# Schematic_AddKEYSTM32_EASYEDA.net
KiCad netlist of a schematic drawn in EasyEDA
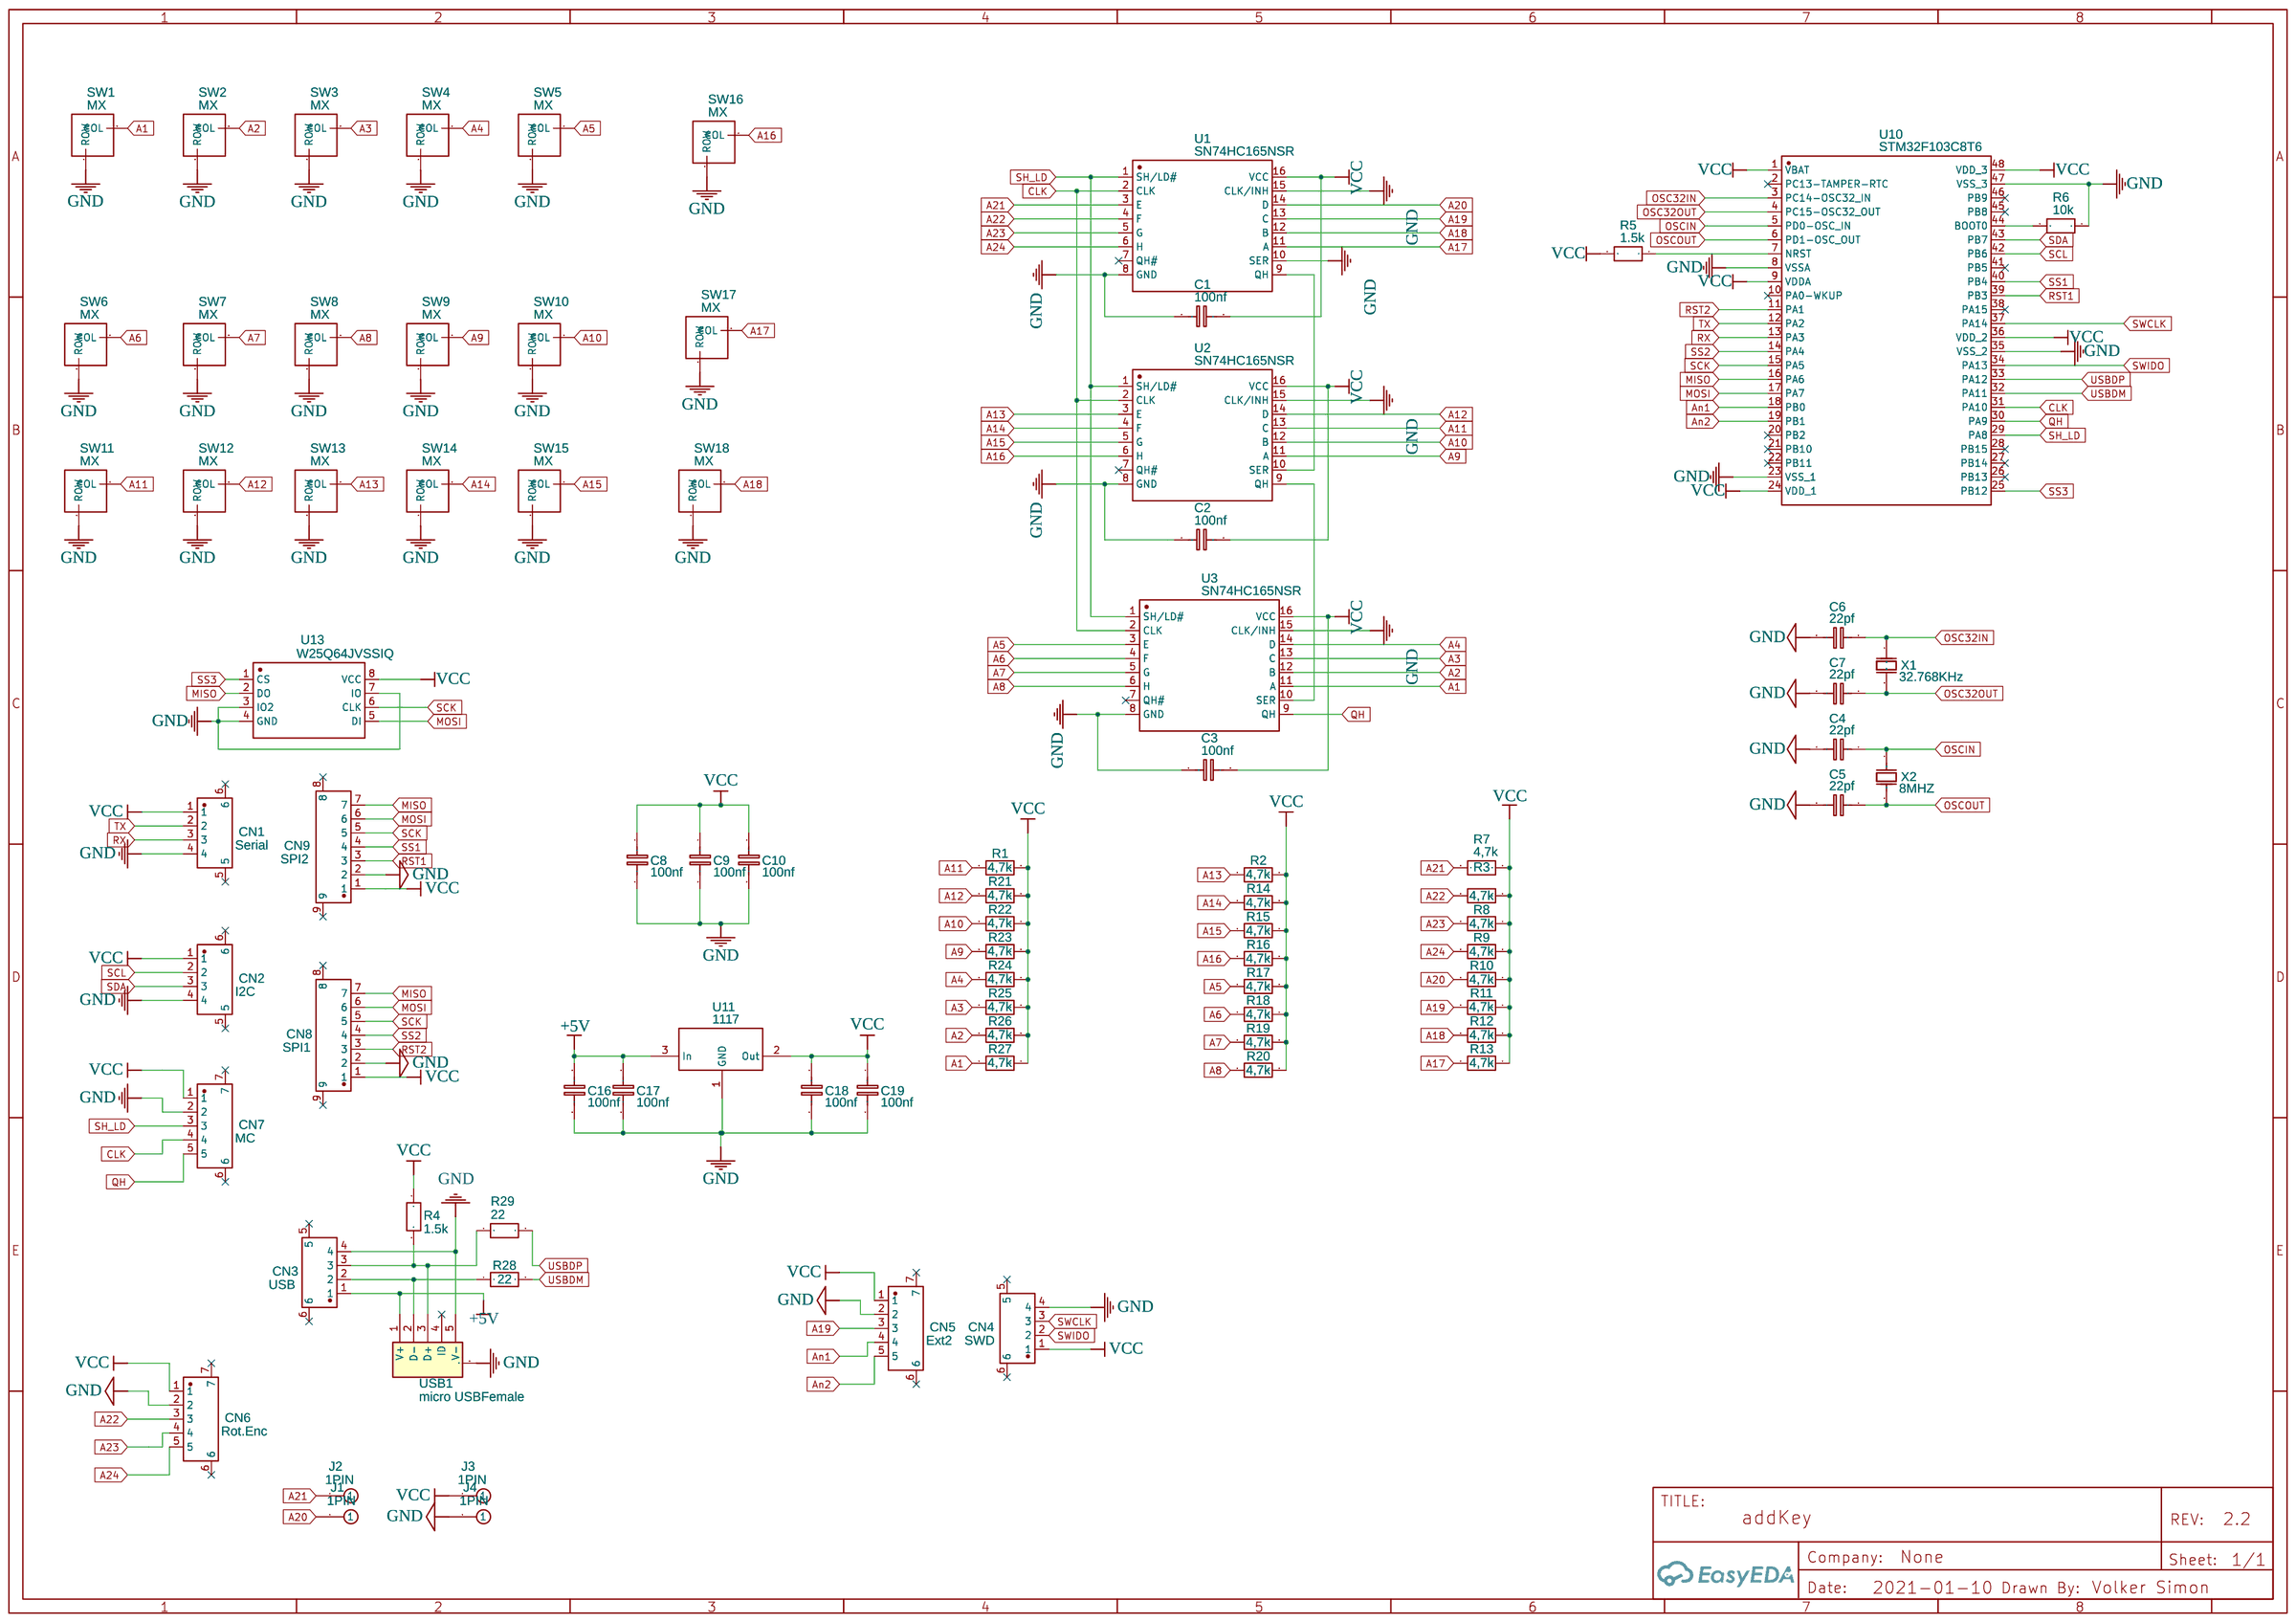
[diagram p0: schematic sheet]

(export (version "E")
  (design (tool "Eeschema 10.0.6"))
  (components
    (comp (ref "C1")
      (value "100nf")
      (fields
        (field (name "BOM_Manufacturer Part") "1206F104M500NT")
        (field (name "BOM_Supplier Part") "C313097")
      )
      (libsource (lib "") (part "Cap_1206_EU_4"))
    )
    (comp (ref "C2")
      (value "100nf")
      (fields
        (field (name "BOM_Manufacturer Part") "1206F104M500NT")
        (field (name "BOM_Supplier Part") "C313097")
      )
      (libsource (lib "") (part "Cap_1206_EU_4"))
    )
    (comp (ref "C3")
      (value "100nf")
      (fields
        (field (name "BOM_Manufacturer Part") "1206F104M500NT")
        (field (name "BOM_Supplier Part") "C313097")
      )
      (libsource (lib "") (part "Cap_1206_EU_3"))
    )
    (comp (ref "C4")
      (value "22pf")
      (fields
        (field (name "BOM_Manufacturer Part") "1206CG220J102NT")
        (field (name "BOM_Supplier Part") "C313096")
      )
      (libsource (lib "") (part "Cap_1206_EU"))
    )
    (comp (ref "C5")
      (value "22pf")
      (fields
        (field (name "BOM_Manufacturer Part") "1206CG220J102NT")
        (field (name "BOM_Supplier Part") "C313096")
      )
      (libsource (lib "") (part "Cap_1206_EU"))
    )
    (comp (ref "C6")
      (value "22pf")
      (fields
        (field (name "BOM_Manufacturer Part") "1206CG220J102NT")
        (field (name "BOM_Supplier Part") "C313096")
      )
      (libsource (lib "") (part "Cap_1206_EU_1"))
    )
    (comp (ref "C7")
      (value "22pf")
      (fields
        (field (name "BOM_Manufacturer Part") "1206CG220J102NT")
        (field (name "BOM_Supplier Part") "C313096")
      )
      (libsource (lib "") (part "Cap_1206_EU_1"))
    )
    (comp (ref "C8")
      (value "100nf")
      (fields
        (field (name "BOM_Manufacturer Part") "1206F104M500NT")
        (field (name "BOM_Supplier Part") "C313097")
      )
      (libsource (lib "") (part "Cap_1206_EU_2"))
    )
    (comp (ref "C9")
      (value "100nf")
      (fields
        (field (name "BOM_Manufacturer Part") "1206F104M500NT")
        (field (name "BOM_Supplier Part") "C313097")
      )
      (libsource (lib "") (part "Cap_1206_EU_2"))
    )
    (comp (ref "C10")
      (value "100nf")
      (fields
        (field (name "BOM_Manufacturer Part") "1206F104M500NT")
        (field (name "BOM_Supplier Part") "C313097")
      )
      (libsource (lib "") (part "Cap_1206_EU_5"))
    )
    (comp (ref "C16")
      (value "100nf")
      (fields
        (field (name "BOM_Manufacturer Part") "1206F104M500NT")
        (field (name "BOM_Supplier Part") "C313097")
      )
      (libsource (lib "") (part "Cap_1206_EU_2"))
    )
    (comp (ref "C17")
      (value "100nf")
      (fields
        (field (name "BOM_Manufacturer Part") "1206F104M500NT")
        (field (name "BOM_Supplier Part") "C313097")
      )
      (libsource (lib "") (part "Cap_1206_EU_2"))
    )
    (comp (ref "C18")
      (value "100nf")
      (fields
        (field (name "BOM_Manufacturer Part") "1206F104M500NT")
        (field (name "BOM_Supplier Part") "C313097")
      )
      (libsource (lib "") (part "Cap_1206_EU_5"))
    )
    (comp (ref "C19")
      (value "100nf")
      (fields
        (field (name "BOM_Manufacturer Part") "1206F104M500NT")
        (field (name "BOM_Supplier Part") "C313097")
      )
      (libsource (lib "") (part "Cap_1206_EU_5"))
    )
    (comp (ref "CN1")
      (value "Serial")
      (fields
        (field (name "BOM_Manufacturer Part") "X1002WRS-04E-LPSWHF")
        (field (name "BOM_Supplier Part") "C437064")
      )
      (libsource (lib "") (part "X1002WRS-04E-LPSWHF"))
    )
    (comp (ref "CN2")
      (value "I2C")
      (fields
        (field (name "BOM_Manufacturer Part") "X1002WRS-04E-LPSWHF")
        (field (name "BOM_Supplier Part") "C437064")
      )
      (libsource (lib "") (part "X1002WRS-04E-LPSWHF"))
    )
    (comp (ref "CN3")
      (value "USB")
      (fields
        (field (name "BOM_Manufacturer Part") "X1002WRS-04E-LPSWHF")
        (field (name "BOM_Supplier Part") "C437064")
      )
      (libsource (lib "") (part "X1002WRS-04E-LPSWHF_1"))
    )
    (comp (ref "CN4")
      (value "SWD")
      (fields
        (field (name "BOM_Manufacturer Part") "X1002WRS-04E-LPSWHF")
        (field (name "BOM_Supplier Part") "C437064")
      )
      (libsource (lib "") (part "X1002WRS-04E-LPSWHF_1"))
    )
    (comp (ref "CN5")
      (value "Ext2")
      (fields
        (field (name "BOM_Manufacturer Part") "X1002WRS-05E-LPSWHF")
        (field (name "BOM_Supplier Part") "C437065")
      )
      (libsource (lib "") (part "X1002WRS-05E-LPSWHF"))
    )
    (comp (ref "CN6")
      (value "Rot.Enc")
      (fields
        (field (name "BOM_Manufacturer Part") "X1002WRS-05E-LPSWHF")
        (field (name "BOM_Supplier Part") "C437065")
      )
      (libsource (lib "") (part "X1002WRS-05E-LPSWHF"))
    )
    (comp (ref "CN7")
      (value "MC")
      (fields
        (field (name "BOM_Manufacturer Part") "X1002WRS-05E-LPSWHF")
        (field (name "BOM_Supplier Part") "C437065")
      )
      (libsource (lib "") (part "X1002WRS-05E-LPSWHF"))
    )
    (comp (ref "CN8")
      (value "SPI1")
      (fields
        (field (name "BOM_Manufacturer Part") "X1002WRS-07E-LPSWHF")
        (field (name "BOM_Supplier Part") "C437067")
      )
      (libsource (lib "") (part "X1002WRS-07E-LPSWHF"))
    )
    (comp (ref "CN9")
      (value "SPI2")
      (fields
        (field (name "BOM_Manufacturer Part") "X1002WRS-07E-LPSWHF")
        (field (name "BOM_Supplier Part") "C437067")
      )
      (libsource (lib "") (part "X1002WRS-07E-LPSWHF"))
    )
    (comp (ref "J1") (value "1PIN") (libsource (lib "") (part "1PIN")))
    (comp (ref "J2") (value "1PIN") (libsource (lib "") (part "1PIN")))
    (comp (ref "J3") (value "1PIN") (libsource (lib "") (part "1PIN")))
    (comp (ref "J4") (value "1PIN") (libsource (lib "") (part "1PIN")))
    (comp (ref "R1")
      (value "4,7k")
      (fields
        (field (name "BOM_Manufacturer Part") "1206W4F4701T5E")
        (field (name "BOM_Supplier Part") "C17936")
      )
      (libsource (lib "") (part "Res_AXIAL-0.3(1/8W)_EU"))
    )
    (comp (ref "R2")
      (value "4,7k")
      (fields
        (field (name "BOM_Manufacturer Part") "1206W4F4701T5E")
        (field (name "BOM_Supplier Part") "C17936")
      )
      (libsource (lib "") (part "Res_AXIAL-0.3(1/8W)_EU"))
    )
    (comp (ref "R3")
      (value "4,7k")
      (fields
        (field (name "BOM_Manufacturer Part") "1206W4F4701T5E")
        (field (name "BOM_Supplier Part") "C17936")
      )
      (libsource (lib "") (part "Res_AXIAL-0.3(1/8W)_EU"))
    )
    (comp (ref "R4") (value "1.5k") (libsource (lib "") (part "Res_AXIAL-0.3(1/8W)_EU_1")))
    (comp (ref "R5") (value "1.5k") (libsource (lib "") (part "Res_AXIAL-0.3(1/8W)_EU")))
    (comp (ref "R6") (value "10k") (libsource (lib "") (part "Res_AXIAL-0.3(1/8W)_EU")))
    (comp (ref "R7")
      (value "4,7k")
      (fields
        (field (name "BOM_Manufacturer Part") "1206W4F4701T5E")
        (field (name "BOM_Supplier Part") "C17936")
      )
      (libsource (lib "") (part "Res_AXIAL-0.3(1/8W)_EU"))
    )
    (comp (ref "R8")
      (value "4,7k")
      (fields
        (field (name "BOM_Manufacturer Part") "1206W4F4701T5E")
        (field (name "BOM_Supplier Part") "C17936")
      )
      (libsource (lib "") (part "Res_AXIAL-0.3(1/8W)_EU"))
    )
    (comp (ref "R9")
      (value "4,7k")
      (fields
        (field (name "BOM_Manufacturer Part") "1206W4F4701T5E")
        (field (name "BOM_Supplier Part") "C17936")
      )
      (libsource (lib "") (part "Res_AXIAL-0.3(1/8W)_EU"))
    )
    (comp (ref "R10")
      (value "4,7k")
      (fields
        (field (name "BOM_Manufacturer Part") "1206W4F4701T5E")
        (field (name "BOM_Supplier Part") "C17936")
      )
      (libsource (lib "") (part "Res_AXIAL-0.3(1/8W)_EU"))
    )
    (comp (ref "R11")
      (value "4,7k")
      (fields
        (field (name "BOM_Manufacturer Part") "1206W4F4701T5E")
        (field (name "BOM_Supplier Part") "C17936")
      )
      (libsource (lib "") (part "Res_AXIAL-0.3(1/8W)_EU"))
    )
    (comp (ref "R12")
      (value "4,7k")
      (fields
        (field (name "BOM_Manufacturer Part") "1206W4F4701T5E")
        (field (name "BOM_Supplier Part") "C17936")
      )
      (libsource (lib "") (part "Res_AXIAL-0.3(1/8W)_EU"))
    )
    (comp (ref "R13")
      (value "4,7k")
      (fields
        (field (name "BOM_Manufacturer Part") "1206W4F4701T5E")
        (field (name "BOM_Supplier Part") "C17936")
      )
      (libsource (lib "") (part "Res_AXIAL-0.3(1/8W)_EU"))
    )
    (comp (ref "R14")
      (value "4,7k")
      (fields
        (field (name "BOM_Manufacturer Part") "1206W4F4701T5E")
        (field (name "BOM_Supplier Part") "C17936")
      )
      (libsource (lib "") (part "Res_AXIAL-0.3(1/8W)_EU"))
    )
    (comp (ref "R15")
      (value "4,7k")
      (fields
        (field (name "BOM_Manufacturer Part") "1206W4F4701T5E")
        (field (name "BOM_Supplier Part") "C17936")
      )
      (libsource (lib "") (part "Res_AXIAL-0.3(1/8W)_EU"))
    )
    (comp (ref "R16")
      (value "4,7k")
      (fields
        (field (name "BOM_Manufacturer Part") "1206W4F4701T5E")
        (field (name "BOM_Supplier Part") "C17936")
      )
      (libsource (lib "") (part "Res_AXIAL-0.3(1/8W)_EU"))
    )
    (comp (ref "R17")
      (value "4,7k")
      (fields
        (field (name "BOM_Manufacturer Part") "1206W4F4701T5E")
        (field (name "BOM_Supplier Part") "C17936")
      )
      (libsource (lib "") (part "Res_AXIAL-0.3(1/8W)_EU"))
    )
    (comp (ref "R18")
      (value "4,7k")
      (fields
        (field (name "BOM_Manufacturer Part") "1206W4F4701T5E")
        (field (name "BOM_Supplier Part") "C17936")
      )
      (libsource (lib "") (part "Res_AXIAL-0.3(1/8W)_EU"))
    )
    (comp (ref "R19")
      (value "4,7k")
      (fields
        (field (name "BOM_Manufacturer Part") "1206W4F4701T5E")
        (field (name "BOM_Supplier Part") "C17936")
      )
      (libsource (lib "") (part "Res_AXIAL-0.3(1/8W)_EU"))
    )
    (comp (ref "R20")
      (value "4,7k")
      (fields
        (field (name "BOM_Manufacturer Part") "1206W4F4701T5E")
        (field (name "BOM_Supplier Part") "C17936")
      )
      (libsource (lib "") (part "Res_AXIAL-0.3(1/8W)_EU"))
    )
    (comp (ref "R21")
      (value "4,7k")
      (fields
        (field (name "BOM_Manufacturer Part") "1206W4F4701T5E")
        (field (name "BOM_Supplier Part") "C17936")
      )
      (libsource (lib "") (part "Res_AXIAL-0.3(1/8W)_EU"))
    )
    (comp (ref "R22")
      (value "4,7k")
      (fields
        (field (name "BOM_Manufacturer Part") "1206W4F4701T5E")
        (field (name "BOM_Supplier Part") "C17936")
      )
      (libsource (lib "") (part "Res_AXIAL-0.3(1/8W)_EU"))
    )
    (comp (ref "R23")
      (value "4,7k")
      (fields
        (field (name "BOM_Manufacturer Part") "1206W4F4701T5E")
        (field (name "BOM_Supplier Part") "C17936")
      )
      (libsource (lib "") (part "Res_AXIAL-0.3(1/8W)_EU"))
    )
    (comp (ref "R24")
      (value "4,7k")
      (fields
        (field (name "BOM_Manufacturer Part") "1206W4F4701T5E")
        (field (name "BOM_Supplier Part") "C17936")
      )
      (libsource (lib "") (part "Res_AXIAL-0.3(1/8W)_EU"))
    )
    (comp (ref "R25")
      (value "4,7k")
      (fields
        (field (name "BOM_Manufacturer Part") "1206W4F4701T5E")
        (field (name "BOM_Supplier Part") "C17936")
      )
      (libsource (lib "") (part "Res_AXIAL-0.3(1/8W)_EU"))
    )
    (comp (ref "R26")
      (value "4,7k")
      (fields
        (field (name "BOM_Manufacturer Part") "1206W4F4701T5E")
        (field (name "BOM_Supplier Part") "C17936")
      )
      (libsource (lib "") (part "Res_AXIAL-0.3(1/8W)_EU"))
    )
    (comp (ref "R27")
      (value "4,7k")
      (fields
        (field (name "BOM_Manufacturer Part") "1206W4F4701T5E")
        (field (name "BOM_Supplier Part") "C17936")
      )
      (libsource (lib "") (part "Res_AXIAL-0.3(1/8W)_EU"))
    )
    (comp (ref "R28") (value "22") (libsource (lib "") (part "Res_AXIAL-0.3(1/8W)_EU_2")))
    (comp (ref "R29") (value "22") (libsource (lib "") (part "Res_AXIAL-0.3(1/8W)_EU_2")))
    (comp (ref "SW1")
      (value "MX")
      (fields (field (name "BOM_Manufacturer Part") "Cherry") (field (name "BOM_Supplier Part") "CH310-ND"))
      (libsource (lib "") (part "CHERRY MX SWITCH 1.0U"))
    )
    (comp (ref "SW2")
      (value "MX")
      (fields (field (name "BOM_Manufacturer Part") "Cherry") (field (name "BOM_Supplier Part") "CH310-ND"))
      (libsource (lib "") (part "CHERRY MX SWITCH 1.0U"))
    )
    (comp (ref "SW3")
      (value "MX")
      (fields (field (name "BOM_Manufacturer Part") "Cherry") (field (name "BOM_Supplier Part") "CH310-ND"))
      (libsource (lib "") (part "CHERRY MX SWITCH 1.0U"))
    )
    (comp (ref "SW4")
      (value "MX")
      (fields (field (name "BOM_Manufacturer Part") "Cherry") (field (name "BOM_Supplier Part") "CH310-ND"))
      (libsource (lib "") (part "CHERRY MX SWITCH 1.0U"))
    )
    (comp (ref "SW5")
      (value "MX")
      (fields (field (name "BOM_Manufacturer Part") "Cherry") (field (name "BOM_Supplier Part") "CH310-ND"))
      (libsource (lib "") (part "CHERRY MX SWITCH 1.0U"))
    )
    (comp (ref "SW6")
      (value "MX")
      (fields (field (name "BOM_Manufacturer Part") "Cherry") (field (name "BOM_Supplier Part") "CH310-ND"))
      (libsource (lib "") (part "CHERRY MX SWITCH 1.0U"))
    )
    (comp (ref "SW7")
      (value "MX")
      (fields (field (name "BOM_Manufacturer Part") "Cherry") (field (name "BOM_Supplier Part") "CH310-ND"))
      (libsource (lib "") (part "CHERRY MX SWITCH 1.0U"))
    )
    (comp (ref "SW8")
      (value "MX")
      (fields (field (name "BOM_Manufacturer Part") "Cherry") (field (name "BOM_Supplier Part") "CH310-ND"))
      (libsource (lib "") (part "CHERRY MX SWITCH 1.0U"))
    )
    (comp (ref "SW9")
      (value "MX")
      (fields (field (name "BOM_Manufacturer Part") "Cherry") (field (name "BOM_Supplier Part") "CH310-ND"))
      (libsource (lib "") (part "CHERRY MX SWITCH 1.0U"))
    )
    (comp (ref "SW10")
      (value "MX")
      (fields (field (name "BOM_Manufacturer Part") "Cherry") (field (name "BOM_Supplier Part") "CH310-ND"))
      (libsource (lib "") (part "CHERRY MX SWITCH 1.0U"))
    )
    (comp (ref "SW11")
      (value "MX")
      (fields (field (name "BOM_Manufacturer Part") "Cherry") (field (name "BOM_Supplier Part") "CH310-ND"))
      (libsource (lib "") (part "CHERRY MX SWITCH 1.0U"))
    )
    (comp (ref "SW12")
      (value "MX")
      (fields (field (name "BOM_Manufacturer Part") "Cherry") (field (name "BOM_Supplier Part") "CH310-ND"))
      (libsource (lib "") (part "CHERRY MX SWITCH 1.0U"))
    )
    (comp (ref "SW13")
      (value "MX")
      (fields (field (name "BOM_Manufacturer Part") "Cherry") (field (name "BOM_Supplier Part") "CH310-ND"))
      (libsource (lib "") (part "CHERRY MX SWITCH 1.0U"))
    )
    (comp (ref "SW14")
      (value "MX")
      (fields (field (name "BOM_Manufacturer Part") "Cherry") (field (name "BOM_Supplier Part") "CH310-ND"))
      (libsource (lib "") (part "CHERRY MX SWITCH 1.0U"))
    )
    (comp (ref "SW15")
      (value "MX")
      (fields (field (name "BOM_Manufacturer Part") "Cherry") (field (name "BOM_Supplier Part") "CH310-ND"))
      (libsource (lib "") (part "CHERRY MX SWITCH 1.0U"))
    )
    (comp (ref "SW16")
      (value "MX")
      (fields (field (name "BOM_Manufacturer Part") "Cherry") (field (name "BOM_Supplier Part") "CH310-ND"))
      (libsource (lib "") (part "CHERRY MX SWITCH 1.0U"))
    )
    (comp (ref "SW17")
      (value "MX")
      (fields (field (name "BOM_Manufacturer Part") "Cherry") (field (name "BOM_Supplier Part") "CH310-ND"))
      (libsource (lib "") (part "CHERRY MX SWITCH 1.0U"))
    )
    (comp (ref "SW18")
      (value "MX")
      (fields (field (name "BOM_Manufacturer Part") "Cherry") (field (name "BOM_Supplier Part") "CH310-ND"))
      (libsource (lib "") (part "CHERRY MX SWITCH 1.0U"))
    )
    (comp (ref "U1")
      (value "SN74HC165NSR")
      (fields (field (name "BOM_Supplier Part") "C129935"))
      (libsource (lib "") (part "Unknown_855_155"))
    )
    (comp (ref "U2")
      (value "SN74HC165NSR")
      (fields (field (name "BOM_Supplier Part") "C129935"))
      (libsource (lib "") (part "Unknown_855_305"))
    )
    (comp (ref "U3")
      (value "SN74HC165NSR")
      (fields (field (name "BOM_Supplier Part") "C129935"))
      (libsource (lib "") (part "Unknown_860_470"))
    )
    (comp (ref "U10")
      (value "STM32F103C8T6")
      (fields (field (name "BOM_Supplier Part") "C8734"))
      (libsource (lib "") (part "STM32F103C8T6"))
    )
    (comp (ref "U11")
      (value "1117")
      (fields (field (name "BOM_Manufacturer Part") "AMS1117-5.0") (field (name "BOM_Supplier Part") "C6186"))
      (libsource (lib "") (part "1117"))
    )
    (comp (ref "U13")
      (value "W25Q64JVSSIQ")
      (fields (field (name "BOM_Supplier Part") "C83140"))
      (libsource (lib "") (part "W25Q64JVSSIQ"))
    )
    (comp (ref "USB1")
      (value "micro USBFemale")
      (fields (field (name "BOM_Supplier Part") "C10418"))
      (libsource (lib "") (part "micro USBFemale"))
    )
    (comp (ref "X1")
      (value "32.768KHz")
      (fields
        (field (name "BOM_Manufacturer Part") "DT-26-32.768K-6pF-20PPM")
        (field (name "BOM_Supplier Part") "C127496")
      )
      (libsource (lib "") (part "DT-26-32.768K-6PF-20PPM"))
    )
    (comp (ref "X2")
      (value "8MHZ")
      (fields
        (field (name "BOM_Manufacturer Part") "49SAC08000182060")
        (field (name "BOM_Supplier Part") "C390747")
      )
      (libsource (lib "") (part "49SAC08000182060"))
    )
  )
  (nets
    (net (code "1") (name "+5V") (class "Default")
      (node (ref "C16") (pin "1") (pinfunction "1_1") (pintype "unspecified"))
      (node (ref "C17") (pin "1") (pinfunction "1_1") (pintype "unspecified"))
      (node (ref "CN3") (pin "1") (pinfunction "1_1") (pintype "unspecified"))
      (node (ref "U11") (pin "3") (pinfunction "In_3") (pintype "unspecified"))
      (node (ref "USB1") (pin "1") (pinfunction "V+_1") (pintype "unspecified"))
    )
    (net (code "2") (name "A1") (class "Default")
      (node (ref "R27") (pin "2") (pinfunction "2_2") (pintype "unspecified"))
      (node (ref "SW1") (pin "C") (pinfunction "COL_C") (pintype "unspecified"))
      (node (ref "U3") (pin "11") (pinfunction "A_11") (pintype "unspecified"))
    )
    (net (code "3") (name "A2") (class "Default")
      (node (ref "R26") (pin "2") (pinfunction "2_2") (pintype "unspecified"))
      (node (ref "SW2") (pin "C") (pinfunction "COL_C") (pintype "unspecified"))
      (node (ref "U3") (pin "12") (pinfunction "B_12") (pintype "unspecified"))
    )
    (net (code "4") (name "A3") (class "Default")
      (node (ref "R25") (pin "2") (pinfunction "2_2") (pintype "unspecified"))
      (node (ref "SW3") (pin "C") (pinfunction "COL_C") (pintype "unspecified"))
      (node (ref "U3") (pin "13") (pinfunction "C_13") (pintype "unspecified"))
    )
    (net (code "5") (name "A4") (class "Default")
      (node (ref "R24") (pin "2") (pinfunction "2_2") (pintype "unspecified"))
      (node (ref "SW4") (pin "C") (pinfunction "COL_C") (pintype "unspecified"))
      (node (ref "U3") (pin "14") (pinfunction "D_14") (pintype "unspecified"))
    )
    (net (code "6") (name "A5") (class "Default")
      (node (ref "R17") (pin "2") (pinfunction "2_2") (pintype "unspecified"))
      (node (ref "SW5") (pin "C") (pinfunction "COL_C") (pintype "unspecified"))
      (node (ref "U3") (pin "3") (pinfunction "E_3") (pintype "unspecified"))
    )
    (net (code "7") (name "A6") (class "Default")
      (node (ref "R18") (pin "2") (pinfunction "2_2") (pintype "unspecified"))
      (node (ref "SW6") (pin "C") (pinfunction "COL_C") (pintype "unspecified"))
      (node (ref "U3") (pin "4") (pinfunction "F_4") (pintype "unspecified"))
    )
    (net (code "8") (name "A7") (class "Default")
      (node (ref "R19") (pin "2") (pinfunction "2_2") (pintype "unspecified"))
      (node (ref "SW7") (pin "C") (pinfunction "COL_C") (pintype "unspecified"))
      (node (ref "U3") (pin "5") (pinfunction "G_5") (pintype "unspecified"))
    )
    (net (code "9") (name "A8") (class "Default")
      (node (ref "R20") (pin "2") (pinfunction "2_2") (pintype "unspecified"))
      (node (ref "SW8") (pin "C") (pinfunction "COL_C") (pintype "unspecified"))
      (node (ref "U3") (pin "6") (pinfunction "H_6") (pintype "unspecified"))
    )
    (net (code "10") (name "A9") (class "Default")
      (node (ref "R23") (pin "2") (pinfunction "2_2") (pintype "unspecified"))
      (node (ref "SW9") (pin "C") (pinfunction "COL_C") (pintype "unspecified"))
      (node (ref "U2") (pin "11") (pinfunction "A_11") (pintype "unspecified"))
    )
    (net (code "11") (name "A10") (class "Default")
      (node (ref "R22") (pin "2") (pinfunction "2_2") (pintype "unspecified"))
      (node (ref "SW10") (pin "C") (pinfunction "COL_C") (pintype "unspecified"))
      (node (ref "U2") (pin "12") (pinfunction "B_12") (pintype "unspecified"))
    )
    (net (code "12") (name "A11") (class "Default")
      (node (ref "R1") (pin "2") (pinfunction "2_2") (pintype "unspecified"))
      (node (ref "SW11") (pin "C") (pinfunction "COL_C") (pintype "unspecified"))
      (node (ref "U2") (pin "13") (pinfunction "C_13") (pintype "unspecified"))
    )
    (net (code "13") (name "A12") (class "Default")
      (node (ref "R21") (pin "2") (pinfunction "2_2") (pintype "unspecified"))
      (node (ref "SW12") (pin "C") (pinfunction "COL_C") (pintype "unspecified"))
      (node (ref "U2") (pin "14") (pinfunction "D_14") (pintype "unspecified"))
    )
    (net (code "14") (name "A13") (class "Default")
      (node (ref "R2") (pin "2") (pinfunction "2_2") (pintype "unspecified"))
      (node (ref "SW13") (pin "C") (pinfunction "COL_C") (pintype "unspecified"))
      (node (ref "U2") (pin "3") (pinfunction "E_3") (pintype "unspecified"))
    )
    (net (code "15") (name "A14") (class "Default")
      (node (ref "R14") (pin "2") (pinfunction "2_2") (pintype "unspecified"))
      (node (ref "SW14") (pin "C") (pinfunction "COL_C") (pintype "unspecified"))
      (node (ref "U2") (pin "4") (pinfunction "F_4") (pintype "unspecified"))
    )
    (net (code "16") (name "A15") (class "Default")
      (node (ref "R15") (pin "2") (pinfunction "2_2") (pintype "unspecified"))
      (node (ref "SW15") (pin "C") (pinfunction "COL_C") (pintype "unspecified"))
      (node (ref "U2") (pin "5") (pinfunction "G_5") (pintype "unspecified"))
    )
    (net (code "17") (name "A16") (class "Default")
      (node (ref "R16") (pin "2") (pinfunction "2_2") (pintype "unspecified"))
      (node (ref "SW16") (pin "C") (pinfunction "COL_C") (pintype "unspecified"))
      (node (ref "U2") (pin "6") (pinfunction "H_6") (pintype "unspecified"))
    )
    (net (code "18") (name "A17") (class "Default")
      (node (ref "R13") (pin "2") (pinfunction "2_2") (pintype "unspecified"))
      (node (ref "SW17") (pin "C") (pinfunction "COL_C") (pintype "unspecified"))
      (node (ref "U1") (pin "11") (pinfunction "A_11") (pintype "unspecified"))
    )
    (net (code "19") (name "A18") (class "Default")
      (node (ref "R12") (pin "2") (pinfunction "2_2") (pintype "unspecified"))
      (node (ref "SW18") (pin "C") (pinfunction "COL_C") (pintype "unspecified"))
      (node (ref "U1") (pin "12") (pinfunction "B_12") (pintype "unspecified"))
    )
    (net (code "20") (name "A19") (class "Default")
      (node (ref "CN5") (pin "3") (pinfunction "3_3") (pintype "unspecified"))
      (node (ref "R11") (pin "2") (pinfunction "2_2") (pintype "unspecified"))
      (node (ref "U1") (pin "13") (pinfunction "C_13") (pintype "unspecified"))
    )
    (net (code "21") (name "A20") (class "Default")
      (node (ref "J1") (pin "1") (pinfunction "1_1") (pintype "unspecified"))
      (node (ref "R10") (pin "2") (pinfunction "2_2") (pintype "unspecified"))
      (node (ref "U1") (pin "14") (pinfunction "D_14") (pintype "unspecified"))
    )
    (net (code "22") (name "A21") (class "Default")
      (node (ref "J2") (pin "1") (pinfunction "1_1") (pintype "unspecified"))
      (node (ref "R7") (pin "2") (pinfunction "2_2") (pintype "unspecified"))
      (node (ref "U1") (pin "3") (pinfunction "E_3") (pintype "unspecified"))
    )
    (net (code "23") (name "A22") (class "Default")
      (node (ref "CN6") (pin "3") (pinfunction "3_3") (pintype "unspecified"))
      (node (ref "R3") (pin "2") (pinfunction "2_2") (pintype "unspecified"))
      (node (ref "U1") (pin "4") (pinfunction "F_4") (pintype "unspecified"))
    )
    (net (code "24") (name "A23") (class "Default")
      (node (ref "CN6") (pin "4") (pinfunction "4_4") (pintype "unspecified"))
      (node (ref "R8") (pin "2") (pinfunction "2_2") (pintype "unspecified"))
      (node (ref "U1") (pin "5") (pinfunction "G_5") (pintype "unspecified"))
    )
    (net (code "25") (name "A24") (class "Default")
      (node (ref "CN6") (pin "5") (pinfunction "5_5") (pintype "unspecified"))
      (node (ref "R9") (pin "2") (pinfunction "2_2") (pintype "unspecified"))
      (node (ref "U1") (pin "6") (pinfunction "H_6") (pintype "unspecified"))
    )
    (net (code "26") (name "An1") (class "Default")
      (node (ref "CN5") (pin "4") (pinfunction "4_4") (pintype "unspecified"))
      (node (ref "U10") (pin "18") (pinfunction "PB0_18") (pintype "unspecified"))
    )
    (net (code "27") (name "An2") (class "Default")
      (node (ref "CN5") (pin "5") (pinfunction "5_5") (pintype "unspecified"))
      (node (ref "U10") (pin "19") (pinfunction "PB1_19") (pintype "unspecified"))
    )
    (net (code "28") (name "CLK") (class "Default")
      (node (ref "CN7") (pin "4") (pinfunction "4_4") (pintype "unspecified"))
      (node (ref "U1") (pin "2") (pinfunction "CLK_2") (pintype "unspecified"))
      (node (ref "U10") (pin "31") (pinfunction "PA10_31") (pintype "unspecified"))
      (node (ref "U2") (pin "2") (pinfunction "CLK_2") (pintype "unspecified"))
      (node (ref "U3") (pin "2") (pinfunction "CLK_2") (pintype "unspecified"))
    )
    (net (code "29") (name "GND") (class "Default")
      (node (ref "C1") (pin "1") (pinfunction "1_1") (pintype "unspecified"))
      (node (ref "C10") (pin "2") (pinfunction "2_2") (pintype "unspecified"))
      (node (ref "C16") (pin "2") (pinfunction "2_2") (pintype "unspecified"))
      (node (ref "C17") (pin "2") (pinfunction "2_2") (pintype "unspecified"))
      (node (ref "C18") (pin "2") (pinfunction "2_2") (pintype "unspecified"))
      (node (ref "C19") (pin "2") (pinfunction "2_2") (pintype "unspecified"))
      (node (ref "C2") (pin "1") (pinfunction "1_1") (pintype "unspecified"))
      (node (ref "C3") (pin "1") (pinfunction "1_1") (pintype "unspecified"))
      (node (ref "C4") (pin "2") (pinfunction "2_2") (pintype "unspecified"))
      (node (ref "C5") (pin "2") (pinfunction "2_2") (pintype "unspecified"))
      (node (ref "C6") (pin "2") (pinfunction "2_2") (pintype "unspecified"))
      (node (ref "C7") (pin "2") (pinfunction "2_2") (pintype "unspecified"))
      (node (ref "C8") (pin "2") (pinfunction "2_2") (pintype "unspecified"))
      (node (ref "C9") (pin "2") (pinfunction "2_2") (pintype "unspecified"))
      (node (ref "CN1") (pin "4") (pinfunction "4_4") (pintype "unspecified"))
      (node (ref "CN2") (pin "4") (pinfunction "4_4") (pintype "unspecified"))
      (node (ref "CN3") (pin "4") (pinfunction "4_4") (pintype "unspecified"))
      (node (ref "CN4") (pin "4") (pinfunction "4_4") (pintype "unspecified"))
      (node (ref "CN5") (pin "2") (pinfunction "2_2") (pintype "unspecified"))
      (node (ref "CN6") (pin "2") (pinfunction "2_2") (pintype "unspecified"))
      (node (ref "CN7") (pin "2") (pinfunction "2_2") (pintype "unspecified"))
      (node (ref "CN8") (pin "2") (pinfunction "2_2") (pintype "unspecified"))
      (node (ref "CN9") (pin "2") (pinfunction "2_2") (pintype "unspecified"))
      (node (ref "J4") (pin "1") (pinfunction "1_1") (pintype "unspecified"))
      (node (ref "R6") (pin "1") (pinfunction "1_1") (pintype "unspecified"))
      (node (ref "SW1") (pin "R") (pinfunction "ROW_R") (pintype "unspecified"))
      (node (ref "SW10") (pin "R") (pinfunction "ROW_R") (pintype "unspecified"))
      (node (ref "SW11") (pin "R") (pinfunction "ROW_R") (pintype "unspecified"))
      (node (ref "SW12") (pin "R") (pinfunction "ROW_R") (pintype "unspecified"))
      (node (ref "SW13") (pin "R") (pinfunction "ROW_R") (pintype "unspecified"))
      (node (ref "SW14") (pin "R") (pinfunction "ROW_R") (pintype "unspecified"))
      (node (ref "SW15") (pin "R") (pinfunction "ROW_R") (pintype "unspecified"))
      (node (ref "SW16") (pin "R") (pinfunction "ROW_R") (pintype "unspecified"))
      (node (ref "SW17") (pin "R") (pinfunction "ROW_R") (pintype "unspecified"))
      (node (ref "SW18") (pin "R") (pinfunction "ROW_R") (pintype "unspecified"))
      (node (ref "SW2") (pin "R") (pinfunction "ROW_R") (pintype "unspecified"))
      (node (ref "SW3") (pin "R") (pinfunction "ROW_R") (pintype "unspecified"))
      (node (ref "SW4") (pin "R") (pinfunction "ROW_R") (pintype "unspecified"))
      (node (ref "SW5") (pin "R") (pinfunction "ROW_R") (pintype "unspecified"))
      (node (ref "SW6") (pin "R") (pinfunction "ROW_R") (pintype "unspecified"))
      (node (ref "SW7") (pin "R") (pinfunction "ROW_R") (pintype "unspecified"))
      (node (ref "SW8") (pin "R") (pinfunction "ROW_R") (pintype "unspecified"))
      (node (ref "SW9") (pin "R") (pinfunction "ROW_R") (pintype "unspecified"))
      (node (ref "U1") (pin "10") (pinfunction "SER_10") (pintype "unspecified"))
      (node (ref "U1") (pin "15") (pinfunction "CLK/INH_15") (pintype "unspecified"))
      (node (ref "U1") (pin "8") (pinfunction "GND_8") (pintype "unspecified"))
      (node (ref "U10") (pin "23") (pinfunction "VSS_1_23") (pintype "unspecified"))
      (node (ref "U10") (pin "35") (pinfunction "VSS_2_35") (pintype "unspecified"))
      (node (ref "U10") (pin "47") (pinfunction "VSS_3_47") (pintype "unspecified"))
      (node (ref "U10") (pin "8") (pinfunction "VSSA_8") (pintype "unspecified"))
      (node (ref "U11") (pin "1") (pinfunction "GND_1") (pintype "unspecified"))
      (node (ref "U13") (pin "3") (pinfunction "IO2_3") (pintype "unspecified"))
      (node (ref "U13") (pin "4") (pinfunction "GND_4") (pintype "unspecified"))
      (node (ref "U13") (pin "7") (pinfunction "IO_7") (pintype "unspecified"))
      (node (ref "U2") (pin "15") (pinfunction "CLK/INH_15") (pintype "unspecified"))
      (node (ref "U2") (pin "8") (pinfunction "GND_8") (pintype "unspecified"))
      (node (ref "U3") (pin "15") (pinfunction "CLK/INH_15") (pintype "unspecified"))
      (node (ref "U3") (pin "8") (pinfunction "GND_8") (pintype "unspecified"))
      (node (ref "USB1") (pin "0") (pinfunction "MTN_0") (pintype "input"))
      (node (ref "USB1") (pin "5") (pinfunction "V-_5") (pintype "unspecified"))
    )
    (net (code "30") (name "MISO") (class "Default")
      (node (ref "CN8") (pin "7") (pinfunction "7_7") (pintype "unspecified"))
      (node (ref "CN9") (pin "7") (pinfunction "7_7") (pintype "unspecified"))
      (node (ref "U10") (pin "16") (pinfunction "PA6_16") (pintype "unspecified"))
      (node (ref "U13") (pin "2") (pinfunction "DO_2") (pintype "unspecified"))
    )
    (net (code "31") (name "MOSI") (class "Default")
      (node (ref "CN8") (pin "6") (pinfunction "6_6") (pintype "unspecified"))
      (node (ref "CN9") (pin "6") (pinfunction "6_6") (pintype "unspecified"))
      (node (ref "U10") (pin "17") (pinfunction "PA7_17") (pintype "unspecified"))
      (node (ref "U13") (pin "5") (pinfunction "DI_5") (pintype "unspecified"))
    )
    (net (code "32") (name "Net-(U1-QH)") (class "Default")
      (node (ref "U1") (pin "9") (pinfunction "QH_9") (pintype "unspecified"))
      (node (ref "U2") (pin "10") (pinfunction "SER_10") (pintype "unspecified"))
    )
    (net (code "33") (name "Net-(U2-QH)") (class "Default")
      (node (ref "U2") (pin "9") (pinfunction "QH_9") (pintype "unspecified"))
      (node (ref "U3") (pin "10") (pinfunction "SER_10") (pintype "unspecified"))
    )
    (net (code "34") (name "Net-(U10-BOOT0)") (class "Default")
      (node (ref "R6") (pin "2") (pinfunction "2_2") (pintype "unspecified"))
      (node (ref "U10") (pin "44") (pinfunction "BOOT0_44") (pintype "unspecified"))
    )
    (net (code "35") (name "Net-(U10-NRST)") (class "Default")
      (node (ref "R5") (pin "1") (pinfunction "1_1") (pintype "unspecified"))
      (node (ref "U10") (pin "7") (pinfunction "NRST_7") (pintype "unspecified"))
    )
    (net (code "36") (name "Net-(USB1-D+)") (class "Default")
      (node (ref "CN3") (pin "3") (pinfunction "3_3") (pintype "unspecified"))
      (node (ref "R29") (pin "1") (pinfunction "1_1") (pintype "unspecified"))
      (node (ref "R4") (pin "2") (pinfunction "2_2") (pintype "unspecified"))
      (node (ref "USB1") (pin "3") (pinfunction "D+_3") (pintype "unspecified"))
    )
    (net (code "37") (name "Net-(USB1-D-)") (class "Default")
      (node (ref "CN3") (pin "2") (pinfunction "2_2") (pintype "unspecified"))
      (node (ref "R28") (pin "1") (pinfunction "1_1") (pintype "unspecified"))
      (node (ref "USB1") (pin "2") (pinfunction "D-_2") (pintype "unspecified"))
    )
    (net (code "38") (name "OSC32IN") (class "Default")
      (node (ref "C6") (pin "1") (pinfunction "1_1") (pintype "unspecified"))
      (node (ref "U10") (pin "3") (pinfunction "PC14-OSC32_IN_3") (pintype "unspecified"))
      (node (ref "X1") (pin "1") (pinfunction "OSC1_1") (pintype "unspecified"))
    )
    (net (code "39") (name "OSC32OUT") (class "Default")
      (node (ref "C7") (pin "1") (pinfunction "1_1") (pintype "unspecified"))
      (node (ref "U10") (pin "4") (pinfunction "PC15-OSC32_OUT_4") (pintype "unspecified"))
      (node (ref "X1") (pin "2") (pinfunction "OSC2_2") (pintype "unspecified"))
    )
    (net (code "40") (name "OSCIN") (class "Default")
      (node (ref "C4") (pin "1") (pinfunction "1_1") (pintype "unspecified"))
      (node (ref "U10") (pin "5") (pinfunction "PD0-OSC_IN_5") (pintype "unspecified"))
      (node (ref "X2") (pin "1") (pinfunction "OSC1_1") (pintype "input"))
    )
    (net (code "41") (name "OSCOUT") (class "Default")
      (node (ref "C5") (pin "1") (pinfunction "1_1") (pintype "unspecified"))
      (node (ref "U10") (pin "6") (pinfunction "PD1-OSC_OUT_6") (pintype "unspecified"))
      (node (ref "X2") (pin "2") (pinfunction "OSC2_2") (pintype "input"))
    )
    (net (code "42") (name "QH") (class "Default")
      (node (ref "CN7") (pin "5") (pinfunction "5_5") (pintype "unspecified"))
      (node (ref "U10") (pin "30") (pinfunction "PA9_30") (pintype "unspecified"))
      (node (ref "U3") (pin "9") (pinfunction "QH_9") (pintype "unspecified"))
    )
    (net (code "43") (name "RST1") (class "Default")
      (node (ref "CN9") (pin "3") (pinfunction "3_3") (pintype "unspecified"))
      (node (ref "U10") (pin "39") (pinfunction "PB3_39") (pintype "unspecified"))
    )
    (net (code "44") (name "RST2") (class "Default")
      (node (ref "CN8") (pin "3") (pinfunction "3_3") (pintype "unspecified"))
      (node (ref "U10") (pin "11") (pinfunction "PA1_11") (pintype "unspecified"))
    )
    (net (code "45") (name "RX") (class "Default")
      (node (ref "CN1") (pin "3") (pinfunction "3_3") (pintype "unspecified"))
      (node (ref "U10") (pin "13") (pinfunction "PA3_13") (pintype "unspecified"))
    )
    (net (code "46") (name "SCK") (class "Default")
      (node (ref "CN8") (pin "5") (pinfunction "5_5") (pintype "unspecified"))
      (node (ref "CN9") (pin "5") (pinfunction "5_5") (pintype "unspecified"))
      (node (ref "U10") (pin "15") (pinfunction "PA5_15") (pintype "unspecified"))
      (node (ref "U13") (pin "6") (pinfunction "CLK_6") (pintype "unspecified"))
    )
    (net (code "47") (name "SCL") (class "Default")
      (node (ref "CN2") (pin "2") (pinfunction "2_2") (pintype "unspecified"))
      (node (ref "U10") (pin "42") (pinfunction "PB6_42") (pintype "unspecified"))
    )
    (net (code "48") (name "SDA") (class "Default")
      (node (ref "CN2") (pin "3") (pinfunction "3_3") (pintype "unspecified"))
      (node (ref "U10") (pin "43") (pinfunction "PB7_43") (pintype "unspecified"))
    )
    (net (code "49") (name "SH_LD") (class "Default")
      (node (ref "CN7") (pin "3") (pinfunction "3_3") (pintype "unspecified"))
      (node (ref "U1") (pin "1") (pinfunction "SH/LD#_1") (pintype "unspecified"))
      (node (ref "U10") (pin "29") (pinfunction "PA8_29") (pintype "unspecified"))
      (node (ref "U2") (pin "1") (pinfunction "SH/LD#_1") (pintype "unspecified"))
      (node (ref "U3") (pin "1") (pinfunction "SH/LD#_1") (pintype "unspecified"))
    )
    (net (code "50") (name "SS1") (class "Default")
      (node (ref "CN9") (pin "4") (pinfunction "4_4") (pintype "unspecified"))
      (node (ref "U10") (pin "40") (pinfunction "PB4_40") (pintype "unspecified"))
    )
    (net (code "51") (name "SS2") (class "Default")
      (node (ref "CN8") (pin "4") (pinfunction "4_4") (pintype "unspecified"))
      (node (ref "U10") (pin "14") (pinfunction "PA4_14") (pintype "unspecified"))
    )
    (net (code "52") (name "SS3") (class "Default")
      (node (ref "U10") (pin "25") (pinfunction "PB12_25") (pintype "unspecified"))
      (node (ref "U13") (pin "1") (pinfunction "CS_1") (pintype "unspecified"))
    )
    (net (code "53") (name "SWCLK") (class "Default")
      (node (ref "CN4") (pin "3") (pinfunction "3_3") (pintype "unspecified"))
      (node (ref "U10") (pin "37") (pinfunction "PA14_37") (pintype "unspecified"))
    )
    (net (code "54") (name "SWIDO") (class "Default")
      (node (ref "CN4") (pin "2") (pinfunction "2_2") (pintype "unspecified"))
      (node (ref "U10") (pin "34") (pinfunction "PA13_34") (pintype "unspecified"))
    )
    (net (code "55") (name "TX") (class "Default")
      (node (ref "CN1") (pin "2") (pinfunction "2_2") (pintype "unspecified"))
      (node (ref "U10") (pin "12") (pinfunction "PA2_12") (pintype "unspecified"))
    )
    (net (code "56") (name "USBDM") (class "Default")
      (node (ref "R28") (pin "2") (pinfunction "2_2") (pintype "unspecified"))
      (node (ref "U10") (pin "32") (pinfunction "PA11_32") (pintype "unspecified"))
    )
    (net (code "57") (name "USBDP") (class "Default")
      (node (ref "R29") (pin "2") (pinfunction "2_2") (pintype "unspecified"))
      (node (ref "U10") (pin "33") (pinfunction "PA12_33") (pintype "unspecified"))
    )
    (net (code "58") (name "VCC") (class "Default")
      (node (ref "C1") (pin "2") (pinfunction "2_2") (pintype "unspecified"))
      (node (ref "C10") (pin "1") (pinfunction "1_1") (pintype "unspecified"))
      (node (ref "C18") (pin "1") (pinfunction "1_1") (pintype "unspecified"))
      (node (ref "C19") (pin "1") (pinfunction "1_1") (pintype "unspecified"))
      (node (ref "C2") (pin "2") (pinfunction "2_2") (pintype "unspecified"))
      (node (ref "C3") (pin "2") (pinfunction "2_2") (pintype "unspecified"))
      (node (ref "C8") (pin "1") (pinfunction "1_1") (pintype "unspecified"))
      (node (ref "C9") (pin "1") (pinfunction "1_1") (pintype "unspecified"))
      (node (ref "CN1") (pin "1") (pinfunction "1_1") (pintype "unspecified"))
      (node (ref "CN2") (pin "1") (pinfunction "1_1") (pintype "unspecified"))
      (node (ref "CN4") (pin "1") (pinfunction "1_1") (pintype "unspecified"))
      (node (ref "CN5") (pin "1") (pinfunction "1_1") (pintype "unspecified"))
      (node (ref "CN6") (pin "1") (pinfunction "1_1") (pintype "unspecified"))
      (node (ref "CN7") (pin "1") (pinfunction "1_1") (pintype "unspecified"))
      (node (ref "CN8") (pin "1") (pinfunction "1_1") (pintype "unspecified"))
      (node (ref "CN9") (pin "1") (pinfunction "1_1") (pintype "unspecified"))
      (node (ref "J3") (pin "1") (pinfunction "1_1") (pintype "unspecified"))
      (node (ref "R1") (pin "1") (pinfunction "1_1") (pintype "unspecified"))
      (node (ref "R10") (pin "1") (pinfunction "1_1") (pintype "unspecified"))
      (node (ref "R11") (pin "1") (pinfunction "1_1") (pintype "unspecified"))
      (node (ref "R12") (pin "1") (pinfunction "1_1") (pintype "unspecified"))
      (node (ref "R13") (pin "1") (pinfunction "1_1") (pintype "unspecified"))
      (node (ref "R14") (pin "1") (pinfunction "1_1") (pintype "unspecified"))
      (node (ref "R15") (pin "1") (pinfunction "1_1") (pintype "unspecified"))
      (node (ref "R16") (pin "1") (pinfunction "1_1") (pintype "unspecified"))
      (node (ref "R17") (pin "1") (pinfunction "1_1") (pintype "unspecified"))
      (node (ref "R18") (pin "1") (pinfunction "1_1") (pintype "unspecified"))
      (node (ref "R19") (pin "1") (pinfunction "1_1") (pintype "unspecified"))
      (node (ref "R2") (pin "1") (pinfunction "1_1") (pintype "unspecified"))
      (node (ref "R20") (pin "1") (pinfunction "1_1") (pintype "unspecified"))
      (node (ref "R21") (pin "1") (pinfunction "1_1") (pintype "unspecified"))
      (node (ref "R22") (pin "1") (pinfunction "1_1") (pintype "unspecified"))
      (node (ref "R23") (pin "1") (pinfunction "1_1") (pintype "unspecified"))
      (node (ref "R24") (pin "1") (pinfunction "1_1") (pintype "unspecified"))
      (node (ref "R25") (pin "1") (pinfunction "1_1") (pintype "unspecified"))
      (node (ref "R26") (pin "1") (pinfunction "1_1") (pintype "unspecified"))
      (node (ref "R27") (pin "1") (pinfunction "1_1") (pintype "unspecified"))
      (node (ref "R3") (pin "1") (pinfunction "1_1") (pintype "unspecified"))
      (node (ref "R4") (pin "1") (pinfunction "1_1") (pintype "unspecified"))
      (node (ref "R5") (pin "2") (pinfunction "2_2") (pintype "unspecified"))
      (node (ref "R7") (pin "1") (pinfunction "1_1") (pintype "unspecified"))
      (node (ref "R8") (pin "1") (pinfunction "1_1") (pintype "unspecified"))
      (node (ref "R9") (pin "1") (pinfunction "1_1") (pintype "unspecified"))
      (node (ref "U1") (pin "16") (pinfunction "VCC_16") (pintype "unspecified"))
      (node (ref "U10") (pin "1") (pinfunction "VBAT_1") (pintype "unspecified"))
      (node (ref "U10") (pin "24") (pinfunction "VDD_1_24") (pintype "unspecified"))
      (node (ref "U10") (pin "36") (pinfunction "VDD_2_36") (pintype "unspecified"))
      (node (ref "U10") (pin "48") (pinfunction "VDD_3_48") (pintype "unspecified"))
      (node (ref "U10") (pin "9") (pinfunction "VDDA_9") (pintype "unspecified"))
      (node (ref "U11") (pin "2") (pinfunction "Out_2") (pintype "unspecified"))
      (node (ref "U13") (pin "8") (pinfunction "VCC_8") (pintype "unspecified"))
      (node (ref "U2") (pin "16") (pinfunction "VCC_16") (pintype "unspecified"))
      (node (ref "U3") (pin "16") (pinfunction "VCC_16") (pintype "unspecified"))
    )
    (net (code "59") (name "unconnected-(CN1-Pad5)") (class "Default")
      (node (ref "CN1") (pin "5") (pinfunction "5_5") (pintype "unspecified+no_connect"))
    )
    (net (code "60") (name "unconnected-(CN1-Pad6)") (class "Default")
      (node (ref "CN1") (pin "6") (pinfunction "6_6") (pintype "unspecified+no_connect"))
    )
    (net (code "61") (name "unconnected-(CN2-Pad5)") (class "Default")
      (node (ref "CN2") (pin "5") (pinfunction "5_5") (pintype "unspecified+no_connect"))
    )
    (net (code "62") (name "unconnected-(CN2-Pad6)") (class "Default")
      (node (ref "CN2") (pin "6") (pinfunction "6_6") (pintype "unspecified+no_connect"))
    )
    (net (code "63") (name "unconnected-(CN3-Pad5)") (class "Default")
      (node (ref "CN3") (pin "5") (pinfunction "5_5") (pintype "unspecified+no_connect"))
    )
    (net (code "64") (name "unconnected-(CN3-Pad6)") (class "Default")
      (node (ref "CN3") (pin "6") (pinfunction "6_6") (pintype "unspecified+no_connect"))
    )
    (net (code "65") (name "unconnected-(CN4-Pad5)") (class "Default")
      (node (ref "CN4") (pin "5") (pinfunction "5_5") (pintype "unspecified+no_connect"))
    )
    (net (code "66") (name "unconnected-(CN4-Pad6)") (class "Default")
      (node (ref "CN4") (pin "6") (pinfunction "6_6") (pintype "unspecified+no_connect"))
    )
    (net (code "67") (name "unconnected-(CN5-Pad6)") (class "Default")
      (node (ref "CN5") (pin "6") (pinfunction "6_6") (pintype "unspecified+no_connect"))
    )
    (net (code "68") (name "unconnected-(CN5-Pad7)") (class "Default")
      (node (ref "CN5") (pin "7") (pinfunction "7_7") (pintype "unspecified+no_connect"))
    )
    (net (code "69") (name "unconnected-(CN6-Pad6)") (class "Default")
      (node (ref "CN6") (pin "6") (pinfunction "6_6") (pintype "unspecified+no_connect"))
    )
    (net (code "70") (name "unconnected-(CN6-Pad7)") (class "Default")
      (node (ref "CN6") (pin "7") (pinfunction "7_7") (pintype "unspecified+no_connect"))
    )
    (net (code "71") (name "unconnected-(CN7-Pad6)") (class "Default")
      (node (ref "CN7") (pin "6") (pinfunction "6_6") (pintype "unspecified+no_connect"))
    )
    (net (code "72") (name "unconnected-(CN7-Pad7)") (class "Default")
      (node (ref "CN7") (pin "7") (pinfunction "7_7") (pintype "unspecified+no_connect"))
    )
    (net (code "73") (name "unconnected-(CN8-Pad8)") (class "Default")
      (node (ref "CN8") (pin "8") (pinfunction "8_8") (pintype "unspecified+no_connect"))
    )
    (net (code "74") (name "unconnected-(CN8-Pad9)") (class "Default")
      (node (ref "CN8") (pin "9") (pinfunction "9_9") (pintype "unspecified+no_connect"))
    )
    (net (code "75") (name "unconnected-(CN9-Pad8)") (class "Default")
      (node (ref "CN9") (pin "8") (pinfunction "8_8") (pintype "unspecified+no_connect"))
    )
    (net (code "76") (name "unconnected-(CN9-Pad9)") (class "Default")
      (node (ref "CN9") (pin "9") (pinfunction "9_9") (pintype "unspecified+no_connect"))
    )
    (net (code "77") (name "unconnected-(U1-QH#-Pad7)") (class "Default")
      (node (ref "U1") (pin "7") (pinfunction "QH#_7") (pintype "unspecified+no_connect"))
    )
    (net (code "78") (name "unconnected-(U2-QH#-Pad7)") (class "Default")
      (node (ref "U2") (pin "7") (pinfunction "QH#_7") (pintype "unspecified+no_connect"))
    )
    (net (code "79") (name "unconnected-(U3-QH#-Pad7)") (class "Default")
      (node (ref "U3") (pin "7") (pinfunction "QH#_7") (pintype "unspecified+no_connect"))
    )
    (net (code "80") (name "unconnected-(U10-PA0-WKUP-Pad10)") (class "Default")
      (node (ref "U10") (pin "10") (pinfunction "PA0-WKUP_10") (pintype "unspecified+no_connect"))
    )
    (net (code "81") (name "unconnected-(U10-PA15-Pad38)") (class "Default")
      (node (ref "U10") (pin "38") (pinfunction "PA15_38") (pintype "unspecified+no_connect"))
    )
    (net (code "82") (name "unconnected-(U10-PB2-Pad20)") (class "Default")
      (node (ref "U10") (pin "20") (pinfunction "PB2_20") (pintype "unspecified+no_connect"))
    )
    (net (code "83") (name "unconnected-(U10-PB5-Pad41)") (class "Default")
      (node (ref "U10") (pin "41") (pinfunction "PB5_41") (pintype "unspecified+no_connect"))
    )
    (net (code "84") (name "unconnected-(U10-PB8-Pad45)") (class "Default")
      (node (ref "U10") (pin "45") (pinfunction "PB8_45") (pintype "unspecified+no_connect"))
    )
    (net (code "85") (name "unconnected-(U10-PB9-Pad46)") (class "Default")
      (node (ref "U10") (pin "46") (pinfunction "PB9_46") (pintype "unspecified+no_connect"))
    )
    (net (code "86") (name "unconnected-(U10-PB10-Pad21)") (class "Default")
      (node (ref "U10") (pin "21") (pinfunction "PB10_21") (pintype "unspecified+no_connect"))
    )
    (net (code "87") (name "unconnected-(U10-PB11-Pad22)") (class "Default")
      (node (ref "U10") (pin "22") (pinfunction "PB11_22") (pintype "unspecified+no_connect"))
    )
    (net (code "88") (name "unconnected-(U10-PB13-Pad26)") (class "Default")
      (node (ref "U10") (pin "26") (pinfunction "PB13_26") (pintype "unspecified+no_connect"))
    )
    (net (code "89") (name "unconnected-(U10-PB14-Pad27)") (class "Default")
      (node (ref "U10") (pin "27") (pinfunction "PB14_27") (pintype "unspecified+no_connect"))
    )
    (net (code "90") (name "unconnected-(U10-PB15-Pad28)") (class "Default")
      (node (ref "U10") (pin "28") (pinfunction "PB15_28") (pintype "unspecified+no_connect"))
    )
    (net (code "91") (name "unconnected-(U10-PC13-TAMPER-RTC-Pad2)") (class "Default")
      (node (ref "U10") (pin "2") (pinfunction "PC13-TAMPER-RTC_2") (pintype "unspecified+no_connect"))
    )
    (net (code "92") (name "unconnected-(USB1-ID-Pad4)") (class "Default")
      (node (ref "USB1") (pin "4") (pinfunction "ID_4") (pintype "unspecified+no_connect"))
    )
  )
)
